# Sensor_Board.net
KiCad netlist of a schematic drawn in Altium Designer
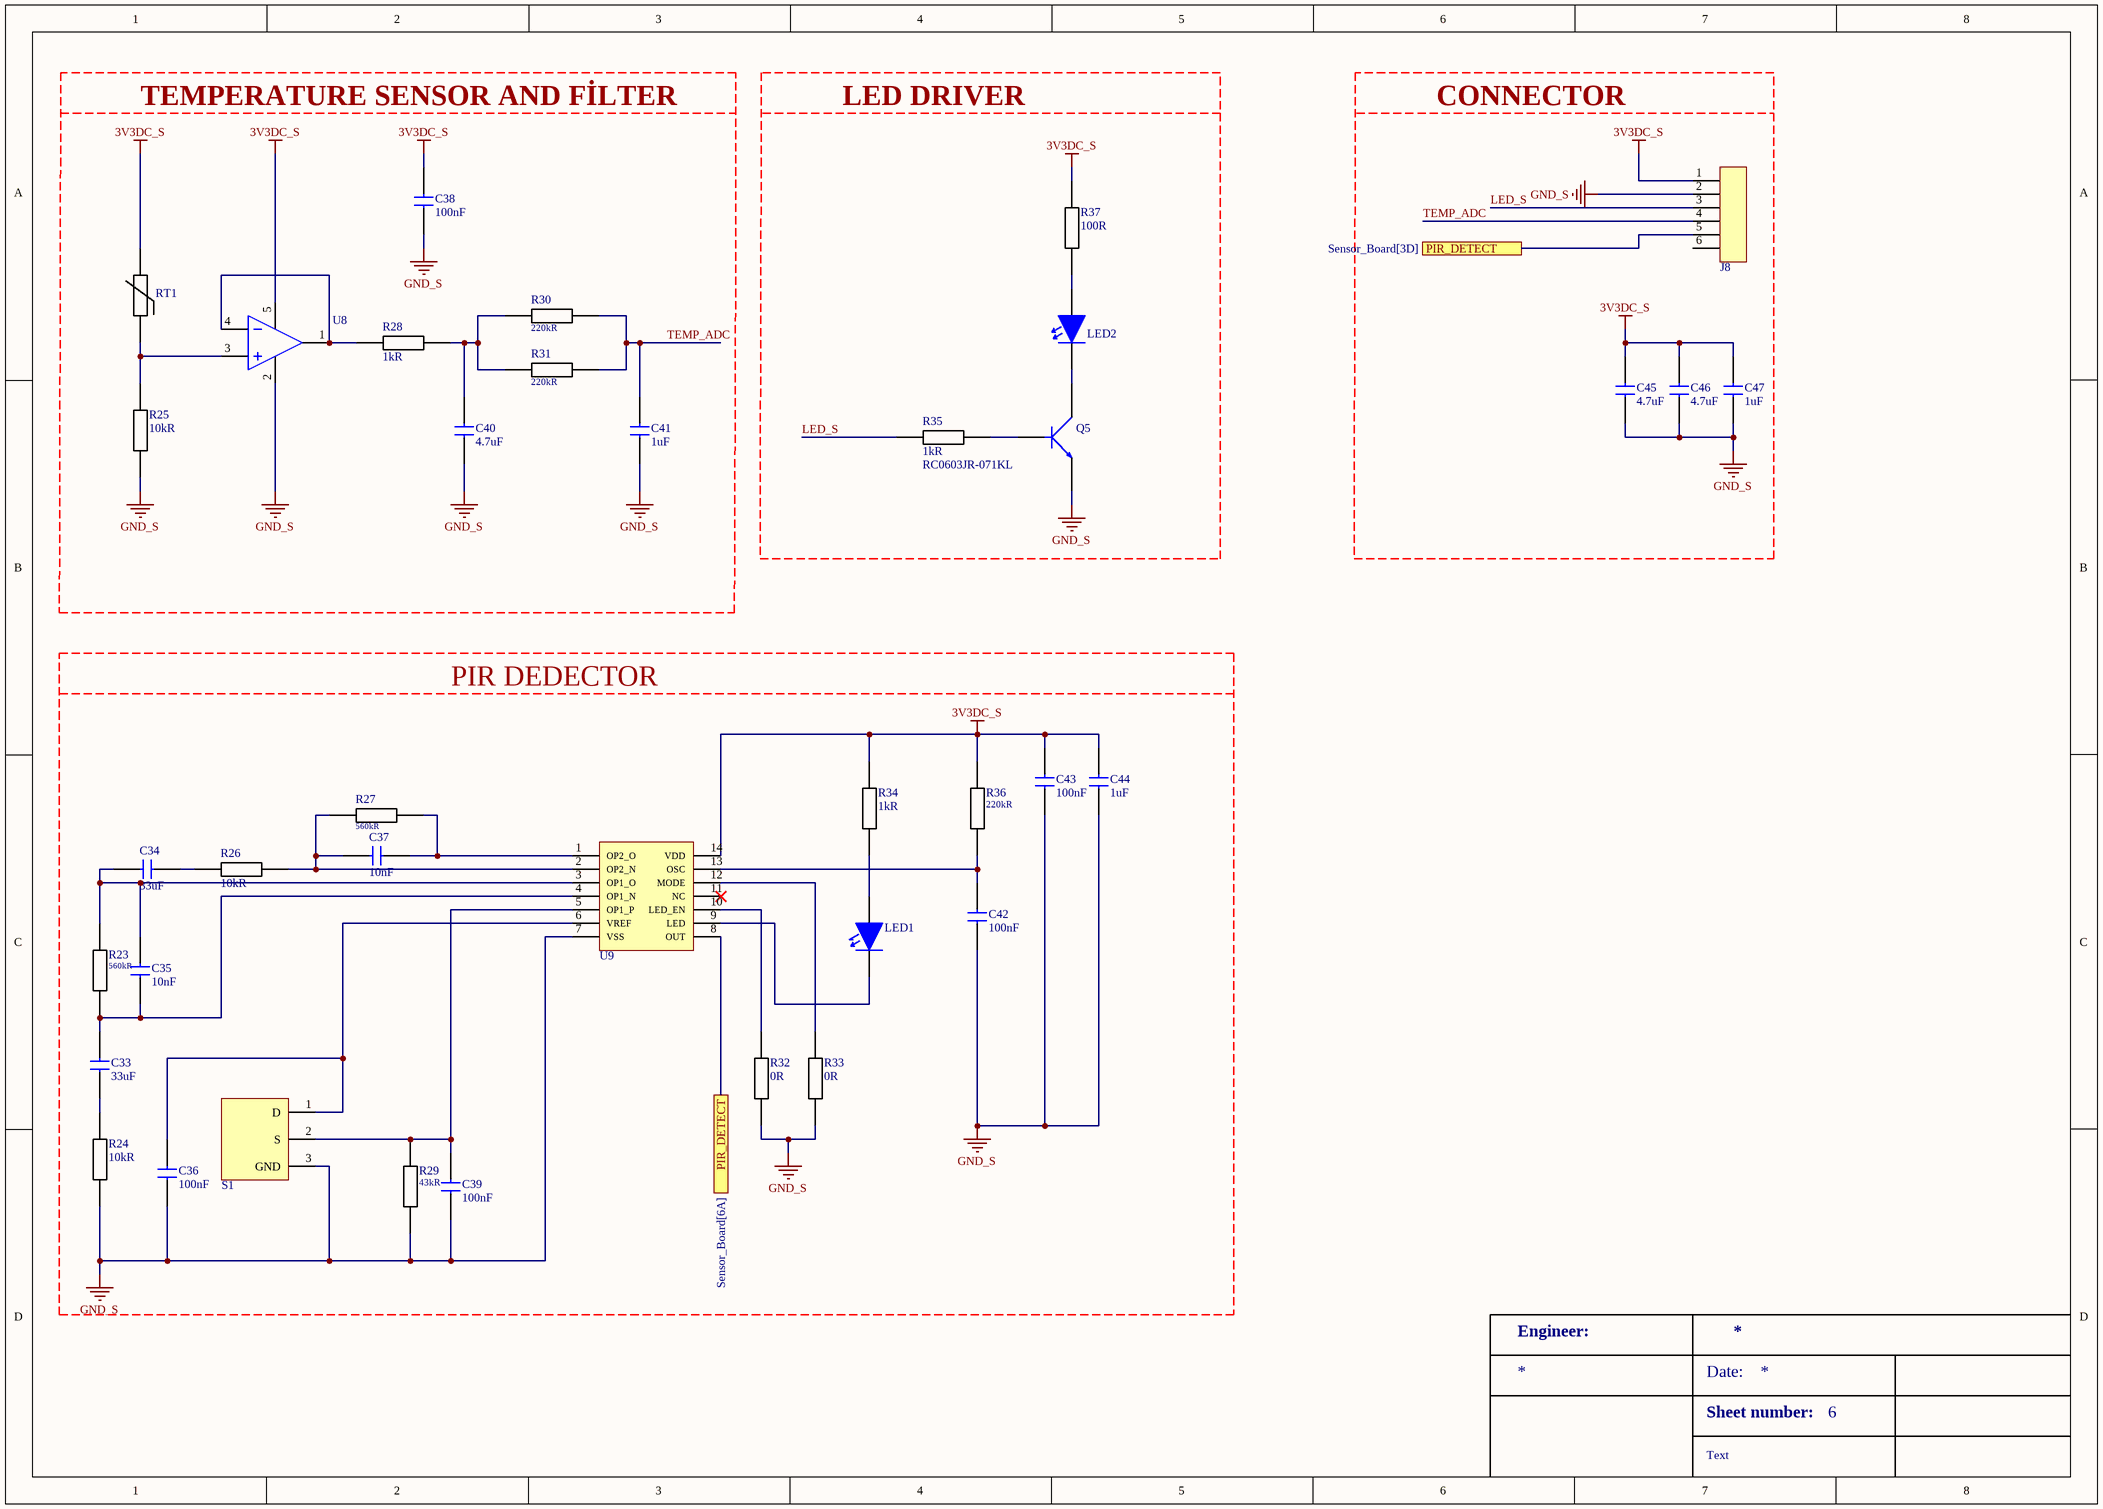
[diagram p0: Sensor_Board.SchDoc]

(export (version "E")
  (design (tool "Eeschema 10.0.6"))
  (components
    (comp (ref "C33")
      (value "33uF")
      (footprint "CAP_1206")
      (description "Ceramic Capacitor, 25V, 20% 33uF, Surface Mount, 1206")
      (fields
        (field (name "MANUFACTURER") "TDK")
        (field (name "MANUFACTURER PART NUMBER") "C3216X5R1E336M160AC")
        (field (name "DESIGNED BY") "Kerem")
      )
      (libsource (lib "library") (part "CAP_CER_33uF_1206"))
    )
    (comp (ref "C34")
      (value "33uF")
      (footprint "CAP_1206")
      (description "Ceramic Capacitor, 25V, 20% 33uF, Surface Mount, 1206")
      (fields
        (field (name "MANUFACTURER") "TDK")
        (field (name "MANUFACTURER PART NUMBER") "C3216X5R1E336M160AC")
        (field (name "DESIGNED BY") "Kerem")
      )
      (libsource (lib "library") (part "CAP_CER_33uF_1206"))
    )
    (comp (ref "C35")
      (value "10nF")
      (footprint "CAP_0603")
      (description "Ceramic Capacitor,16V, 10%, 0.01uF, Surface Mount, 0603")
      (fields
        (field (name "MANUFACTURER") "Walsin Technologies")
        (field (name "MANUFACTURER PART NUMBER") "0603B103K160CT")
        (field (name "DESIGNED BY") "Kerem")
      )
      (libsource (lib "library") (part "CAP_CER_10nF_0603"))
    )
    (comp (ref "C36")
      (value "100nF")
      (footprint "CAP_0805")
      (description "Ceramic Capacitor,50V, %10, 0.1uF, Surface Mount, 0805")
      (fields
        (field (name "MANUFACTURER") "Samsung")
        (field (name "MANUFACTURER PART NUMBER") "CL21B104KBCNNNC")
        (field (name "DESIGNED BY") "Kerem")
      )
      (libsource (lib "library") (part "CAP_CER_100nF_0805"))
    )
    (comp (ref "C37")
      (value "10nF")
      (footprint "CAP_0603")
      (description "Ceramic Capacitor,16V, 10%, 0.01uF, Surface Mount, 0603")
      (fields
        (field (name "MANUFACTURER") "Walsin Technologies")
        (field (name "MANUFACTURER PART NUMBER") "0603B103K160CT")
        (field (name "DESIGNED BY") "Kerem")
      )
      (libsource (lib "library") (part "CAP_CER_10nF_0603"))
    )
    (comp (ref "C38")
      (value "100nF")
      (footprint "CAP_0805")
      (description "Ceramic Capacitor,50V, %10, 0.1uF, Surface Mount, 0805")
      (fields
        (field (name "MANUFACTURER") "Samsung")
        (field (name "MANUFACTURER PART NUMBER") "CL21B104KBCNNNC")
        (field (name "DESIGNED BY") "Kerem")
      )
      (libsource (lib "library") (part "CAP_CER_100nF_0805"))
    )
    (comp (ref "C39")
      (value "100nF")
      (footprint "CAP_0805")
      (description "Ceramic Capacitor,50V, %10, 0.1uF, Surface Mount, 0805")
      (fields
        (field (name "MANUFACTURER") "Samsung")
        (field (name "MANUFACTURER PART NUMBER") "CL21B104KBCNNNC")
        (field (name "DESIGNED BY") "Kerem")
      )
      (libsource (lib "library") (part "CAP_CER_100nF_0805"))
    )
    (comp (ref "C40")
      (value "4.7uF")
      (footprint "CAP_0805")
      (description "CAP CER 4.7uF,%10, Surface Mount, 0805")
      (fields
        (field (name "MANUFACTURER") "Samsung")
        (field (name "MANUFACTURER PART NUMBER") "CL21A475KAQNNNE")
        (field (name "DESIGNED BY") "Kerem")
      )
      (libsource (lib "library") (part "CAP_CER_4.7uF_0805"))
    )
    (comp (ref "C41")
      (value "1uF")
      (footprint "CAP_0805")
      (description "Cap CER, 1uF, 16V, 0805;")
      (fields
        (field (name "MANUFACTURER") "KEMET")
        (field (name "MANUFACTURER PART NUMBER") "CHA08C105K4RXL7189")
        (field (name "DESIGNED BY") "Kerem")
      )
      (libsource (lib "library") (part "CAP_CER_1uF_0805"))
    )
    (comp (ref "C42")
      (value "100nF")
      (footprint "CAP_0805")
      (description "Ceramic Capacitor,50V, %10, 0.1uF, Surface Mount, 0805")
      (fields
        (field (name "MANUFACTURER") "Samsung")
        (field (name "MANUFACTURER PART NUMBER") "CL21B104KBCNNNC")
        (field (name "DESIGNED BY") "Kerem")
      )
      (libsource (lib "library") (part "CAP_CER_100nF_0805"))
    )
    (comp (ref "C43")
      (value "100nF")
      (footprint "CAP_0805")
      (description "Ceramic Capacitor,50V, %10, 0.1uF, Surface Mount, 0805")
      (fields
        (field (name "MANUFACTURER") "Samsung")
        (field (name "MANUFACTURER PART NUMBER") "CL21B104KBCNNNC")
        (field (name "DESIGNED BY") "Kerem")
      )
      (libsource (lib "library") (part "CAP_CER_100nF_0805"))
    )
    (comp (ref "C44")
      (value "1uF")
      (footprint "CAP_0805")
      (description "Cap CER, 1uF, 16V, 0805;")
      (fields
        (field (name "MANUFACTURER") "KEMET")
        (field (name "MANUFACTURER PART NUMBER") "CHA08C105K4RXL7189")
        (field (name "DESIGNED BY") "Kerem")
      )
      (libsource (lib "library") (part "CAP_CER_1uF_0805"))
    )
    (comp (ref "C45")
      (value "4.7uF")
      (footprint "CAP_0805")
      (description "CAP CER 4.7uF,%10, Surface Mount, 0805")
      (fields
        (field (name "MANUFACTURER") "Samsung")
        (field (name "MANUFACTURER PART NUMBER") "CL21A475KAQNNNE")
        (field (name "DESIGNED BY") "Kerem")
      )
      (libsource (lib "library") (part "CAP_CER_4.7uF_0805"))
    )
    (comp (ref "C46")
      (value "4.7uF")
      (footprint "CAP_0805")
      (description "CAP CER 4.7uF,%10, Surface Mount, 0805")
      (fields
        (field (name "MANUFACTURER") "Samsung")
        (field (name "MANUFACTURER PART NUMBER") "CL21A475KAQNNNE")
        (field (name "DESIGNED BY") "Kerem")
      )
      (libsource (lib "library") (part "CAP_CER_4.7uF_0805"))
    )
    (comp (ref "C47")
      (value "1uF")
      (footprint "CAP_0805")
      (description "Cap CER, 1uF, 16V, 0805;")
      (fields
        (field (name "MANUFACTURER") "KEMET")
        (field (name "MANUFACTURER PART NUMBER") "CHA08C105K4RXL7189")
        (field (name "DESIGNED BY") "Kerem")
      )
      (libsource (lib "library") (part "CAP_CER_1uF_0805"))
    )
    (comp (ref "J8")
      (value "64800611622")
      (footprint "64800611622")
      (description "WR-WTB Wire-to-Board Connectors 1.50 mm")
      (fields (field (name "MANUFACTURER") "Wurth Electronics") (field (name "DESIGNED BY") "Kerem"))
      (libsource (lib "library") (part "64800611622_CONN_6PINS"))
    )
    (comp (ref "LED1")
      (value "LTST-C171GKT")
      (footprint "LED_GREEN 0805")
      (description "Single Color LED, Green, Water Clear, 1.4mm")
      (fields (field (name "MANUFACTURER") "Vishay Lite-On") (field (name "DESIGNED BY") "Kerem"))
      (libsource (lib "library") (part "LED_GREEN_0805"))
    )
    (comp (ref "LED2")
      (value "LH R974-LP-1")
      (footprint "LED_RED 0805")
      (fields (field (name "DESIGNED BY") "Kerem"))
      (libsource (lib "library") (part "LED_RED_0805"))
    )
    (comp (ref "Q5")
      (value "MMBT3904-7-F")
      (footprint "SOT-23F")
      (description "Small Signal Bipolar Transistor, 0.2A I(C), 40V V(BR)CEO, 1-Element, NPN, Silicon")
      (fields (field (name "MANUFACTURER") "Diodes Zetex") (field (name "DESIGNED BY") "Kerem"))
      (libsource (lib "library") (part "MMBT3904-7-F"))
    )
    (comp (ref "R23")
      (value "560kR")
      (footprint "RES_0603")
      (description "0.1W, 560000ohm, 75V, 5%, Surface Mount, 0603")
      (fields
        (field (name "MANUFACTURER") "Yageo")
        (field (name "MANUFACTURER PART NUMBER") "RC0603JR-07560KL")
        (field (name "DESIGNED BY") "Kerem")
      )
      (libsource (lib "library") (part "RES_560K OHM_0603"))
    )
    (comp (ref "R24")
      (value "10kR")
      (footprint "RES_0603")
      (fields
        (field (name "MANUFACTURER") "Yageo")
        (field (name "MANUFACTURER PART NUMBER") "RC0603FR-0710KL")
        (field (name "TOLERANCE") "1%")
        (field (name "DESIGNED BY") "Kerem")
      )
      (libsource (lib "library") (part "RES 10K OHM 0603"))
    )
    (comp (ref "R25")
      (value "10kR")
      (footprint "RES_0603")
      (fields
        (field (name "MANUFACTURER") "Yageo")
        (field (name "MANUFACTURER PART NUMBER") "RC0603FR-0710KL")
        (field (name "TOLERANCE") "1%")
        (field (name "DESIGNED BY") "Kerem")
      )
      (libsource (lib "library") (part "RES 10K OHM 0603"))
    )
    (comp (ref "R26")
      (value "10kR")
      (footprint "RES_0603")
      (fields
        (field (name "MANUFACTURER") "Yageo")
        (field (name "MANUFACTURER PART NUMBER") "RC0603FR-0710KL")
        (field (name "TOLERANCE") "1%")
        (field (name "DESIGNED BY") "Kerem")
      )
      (libsource (lib "library") (part "RES 10K OHM 0603"))
    )
    (comp (ref "R27")
      (value "560kR")
      (footprint "RES_0603")
      (description "0.1W, 560000ohm, 75V, 5%, Surface Mount, 0603")
      (fields
        (field (name "MANUFACTURER") "Yageo")
        (field (name "MANUFACTURER PART NUMBER") "RC0603JR-07560KL")
        (field (name "DESIGNED BY") "Kerem")
      )
      (libsource (lib "library") (part "RES_560K OHM_0603"))
    )
    (comp (ref "R28")
      (value "1kR")
      (footprint "RES_0603")
      (description "0.1W, 1000ohm, 75V, 5%, Surface Mount, 0603")
      (fields
        (field (name "MANUFACTURER") "Yageo")
        (field (name "MANUFACTURER PART NUMBER") "RC0603JR-071KL")
        (field (name "DESIGNED BY") "Kerem")
      )
      (libsource (lib "library") (part "RES_1K OHM_0603"))
    )
    (comp (ref "R29")
      (value "43kR")
      (footprint "RES_0603")
      (description "0.1W, 43000ohm, 75V, 5%, Surface Mount, 0603")
      (fields
        (field (name "MANUFACTURER") "Yageo")
        (field (name "MANUFACTURER PART NUMBER") "RC0603JR-0743KL")
        (field (name "DESIGNED BY") "Kerem")
      )
      (libsource (lib "library") (part "RES_43K OHM_0603"))
    )
    (comp (ref "R30")
      (value "220kR")
      (footprint "RES_0603")
      (description "0.1W, 220000ohm, 75V, 5%, Surface Mount, 0603")
      (fields
        (field (name "MANUFACTURER") "Yageo")
        (field (name "MANUFACTURER PART NUMBER") "RC0603JR-07220KL")
        (field (name "DESIGNED BY") "Kerem")
      )
      (libsource (lib "library") (part "RES_220K OHM_0603"))
    )
    (comp (ref "R31")
      (value "220kR")
      (footprint "RES_0603")
      (description "0.1W, 220000ohm, 75V, 5%, Surface Mount, 0603")
      (fields
        (field (name "MANUFACTURER") "Yageo")
        (field (name "MANUFACTURER PART NUMBER") "RC0603JR-07220KL")
        (field (name "DESIGNED BY") "Kerem")
      )
      (libsource (lib "library") (part "RES_220K OHM_0603"))
    )
    (comp (ref "R32")
      (value "0R")
      (footprint "RES_0603")
      (description "Metal Glaze/thick Film, 0.1W, 0ohm, Surface Mount, 0603")
      (fields
        (field (name "MANUFACTURER") "Yageo")
        (field (name "MANUFACTURER PART NUMBER") "RC0603JR-070RL")
        (field (name "DESIGNED BY") "Kerem")
      )
      (libsource (lib "library") (part "RES_0 OHM_0603"))
    )
    (comp (ref "R33")
      (value "0R")
      (footprint "RES_0603")
      (description "Metal Glaze/thick Film, 0.1W, 0ohm, Surface Mount, 0603")
      (fields
        (field (name "MANUFACTURER") "Yageo")
        (field (name "MANUFACTURER PART NUMBER") "RC0603JR-070RL")
        (field (name "DESIGNED BY") "Kerem")
      )
      (libsource (lib "library") (part "RES_0 OHM_0603"))
    )
    (comp (ref "R34")
      (value "1kR")
      (footprint "RES_0603")
      (description "0.1W, 1000ohm, 75V, 5%, Surface Mount, 0603")
      (fields
        (field (name "MANUFACTURER") "Yageo")
        (field (name "MANUFACTURER PART NUMBER") "RC0603JR-071KL")
        (field (name "DESIGNED BY") "Kerem")
      )
      (libsource (lib "library") (part "RES_1K OHM_0603"))
    )
    (comp (ref "R35")
      (value "RC0603JR-071KL")
      (footprint "RES_0603")
      (description "0.1W, 1000ohm, 75V, 5%, Surface Mount, 0603")
      (fields
        (field (name "MANUFACTURER") "Yageo")
        (field (name "TOLERANCE") "5%")
        (field (name "ALTIUM_VALUE") "1kR")
        (field (name "DESIGNED BY") "Kerem")
      )
      (libsource (lib "library") (part "RES_1K OHM_0603"))
    )
    (comp (ref "R36")
      (value "220kR")
      (footprint "RES_0603")
      (description "0.1W, 220000ohm, 75V, 5%, Surface Mount, 0603")
      (fields
        (field (name "MANUFACTURER") "Yageo")
        (field (name "MANUFACTURER PART NUMBER") "RC0603JR-07220KL")
        (field (name "DESIGNED BY") "Kerem")
      )
      (libsource (lib "library") (part "RES_220K OHM_0603"))
    )
    (comp (ref "R37")
      (value "100R")
      (footprint "RES_0603")
      (description "0.1W, 100ohm, 75V, 1% Surface Mount, 0603")
      (fields
        (field (name "MANUFACTURER") "Yageo")
        (field (name "MANUFACTURER PART NUMBER") "RC0603FR-07100RL")
        (field (name "DESIGNED BY") "Kerem")
      )
      (libsource (lib "library") (part "RES_100 OHM_0603"))
    )
    (comp (ref "RT1")
      (value "TFPT 1206L1002FM")
      (footprint "RES-1206")
      (description "PTC Thermistor, 10000ohm, Surface Mount 1206")
      (fields
        (field (name "MANUFACTURER") "Vishay Dale")
        (field (name "MANUFACTURER PART NUMBER") "TFPT1206L1002FM")
        (field (name "DESIGNED BY") "Kerem")
      )
      (libsource (lib "library") (part "TFPT 1206L1002FM"))
    )
    (comp (ref "S1")
      (value "LHI 878/3902")
      (footprint "LHI 878/3902")
      (description "Sensor Pyro Detector Dual Motion")
      (fields
        (field (name "MANUFACTURER") "Excelitas Technology")
        (field (name "DESIGNED BY") "Kerem")
        (field (name "COMPONENTLINK1URL") "file:///C:/Users/KEREM/Downloads/PYD_1388___7083_Dual_Element_Pyrodetector_Datasheet.pdf")
      )
      (libsource (lib "library") (part "LHI 878/3902"))
    )
    (comp (ref "U8")
      (value "OPA314AIDBVR")
      (footprint "SOT23-5")
      (description "Operational Amplifier, 1 Func, 2500uV Offset-Max, CMOS, PDSO5")
      (fields
        (field (name "MANUFACTURER") "Texas Instruments")
        (field (name "POWER") "No")
        (field (name "DESIGNED BY") "Kerem")
      )
      (libsource (lib "library") (part "OPA314"))
    )
    (comp (ref "U9")
      (value "NCS36000DRG")
      (footprint "SOIC14")
      (description "PIR Controller Analog Circuit, 1 Func, CMOS, PDSO14")
      (fields (field (name "MANUFACTURER") "ON Semiconductor") (field (name "DESIGNED BY") "Kerem"))
      (libsource (lib "library") (part "NCS36000"))
    )
  )
  (nets
    (net (code "1") (name "/LED_S") (class "Default")
      (node (ref "J8") (pin "3") (pinfunction "3_3") (pintype "passive"))
      (node (ref "R35") (pin "1") (pinfunction "1_1") (pintype "passive"))
    )
    (net (code "2") (name "/PIR_DETECT") (class "Default")
      (node (ref "J8") (pin "5") (pinfunction "5_5") (pintype "passive"))
      (node (ref "U9") (pin "8") (pinfunction "OUT_8") (pintype "passive"))
    )
    (net (code "3") (name "/TEMP_ADC") (class "Default")
      (node (ref "C41") (pin "2") (pinfunction "2_2") (pintype "passive"))
      (node (ref "J8") (pin "4") (pinfunction "4_4") (pintype "passive"))
      (node (ref "R30") (pin "2") (pinfunction "2_2") (pintype "passive"))
      (node (ref "R31") (pin "2") (pinfunction "2_2") (pintype "passive"))
    )
    (net (code "4") (name "3V3DC_S") (class "Default")
      (node (ref "C38") (pin "2") (pinfunction "2_2") (pintype "passive"))
      (node (ref "C43") (pin "2") (pinfunction "2_2") (pintype "passive"))
      (node (ref "C44") (pin "2") (pinfunction "2_2") (pintype "passive"))
      (node (ref "C45") (pin "2") (pinfunction "2_2") (pintype "passive"))
      (node (ref "C46") (pin "2") (pinfunction "2_2") (pintype "passive"))
      (node (ref "C47") (pin "2") (pinfunction "2_2") (pintype "passive"))
      (node (ref "J8") (pin "1") (pinfunction "1_1") (pintype "passive"))
      (node (ref "R34") (pin "2") (pinfunction "2_2") (pintype "passive"))
      (node (ref "R36") (pin "1") (pinfunction "1_1") (pintype "passive"))
      (node (ref "R37") (pin "2") (pinfunction "2_2") (pintype "passive"))
      (node (ref "RT1") (pin "2") (pinfunction "2_2") (pintype "passive"))
      (node (ref "U8") (pin "5") (pinfunction "5_5") (pintype "passive"))
      (node (ref "U9") (pin "14") (pinfunction "VDD_14") (pintype "passive"))
    )
    (net (code "5") (name "GND_S") (class "Default")
      (node (ref "C36") (pin "1") (pinfunction "1_1") (pintype "passive"))
      (node (ref "C38") (pin "1") (pinfunction "1_1") (pintype "passive"))
      (node (ref "C39") (pin "1") (pinfunction "1_1") (pintype "passive"))
      (node (ref "C40") (pin "1") (pinfunction "1_1") (pintype "passive"))
      (node (ref "C41") (pin "1") (pinfunction "1_1") (pintype "passive"))
      (node (ref "C42") (pin "1") (pinfunction "1_1") (pintype "passive"))
      (node (ref "C43") (pin "1") (pinfunction "1_1") (pintype "passive"))
      (node (ref "C44") (pin "1") (pinfunction "1_1") (pintype "passive"))
      (node (ref "C45") (pin "1") (pinfunction "1_1") (pintype "passive"))
      (node (ref "C46") (pin "1") (pinfunction "1_1") (pintype "passive"))
      (node (ref "C47") (pin "1") (pinfunction "1_1") (pintype "passive"))
      (node (ref "J8") (pin "2") (pinfunction "2_2") (pintype "passive"))
      (node (ref "Q5") (pin "2") (pinfunction "E_2") (pintype "passive"))
      (node (ref "R24") (pin "1") (pinfunction "1_1") (pintype "passive"))
      (node (ref "R25") (pin "1") (pinfunction "1_1") (pintype "passive"))
      (node (ref "R29") (pin "1") (pinfunction "1_1") (pintype "passive"))
      (node (ref "R32") (pin "1") (pinfunction "1_1") (pintype "passive"))
      (node (ref "R33") (pin "1") (pinfunction "1_1") (pintype "passive"))
      (node (ref "S1") (pin "3") (pinfunction "GND_3") (pintype "passive"))
      (node (ref "U8") (pin "2") (pinfunction "2_2") (pintype "passive"))
      (node (ref "U9") (pin "7") (pinfunction "VSS_7") (pintype "passive"))
    )
    (net (code "6") (name "Net-(C33-Pad1)") (class "Default")
      (node (ref "C33") (pin "1") (pinfunction "1_1") (pintype "passive"))
      (node (ref "R24") (pin "2") (pinfunction "2_2") (pintype "passive"))
    )
    (net (code "7") (name "Net-(C34-Pad2)") (class "Default")
      (node (ref "C34") (pin "2") (pinfunction "2_2") (pintype "passive"))
      (node (ref "R26") (pin "1") (pinfunction "1_1") (pintype "passive"))
    )
    (net (code "8") (name "Net-(C40-Pad2)") (class "Default")
      (node (ref "C40") (pin "2") (pinfunction "2_2") (pintype "passive"))
      (node (ref "R28") (pin "2") (pinfunction "2_2") (pintype "passive"))
      (node (ref "R30") (pin "1") (pinfunction "1_1") (pintype "passive"))
      (node (ref "R31") (pin "1") (pinfunction "1_1") (pintype "passive"))
    )
    (net (code "9") (name "Net-(LED1-Pad2)") (class "Default")
      (node (ref "LED1") (pin "2") (pinfunction "2_2") (pintype "passive"))
      (node (ref "R34") (pin "1") (pinfunction "1_1") (pintype "passive"))
    )
    (net (code "10") (name "Net-(LED2-Pad2)") (class "Default")
      (node (ref "LED2") (pin "2") (pinfunction "2_2") (pintype "passive"))
      (node (ref "R37") (pin "1") (pinfunction "1_1") (pintype "passive"))
    )
    (net (code "11") (name "Net-(Q5-B)") (class "Default")
      (node (ref "Q5") (pin "1") (pinfunction "B_1") (pintype "passive"))
      (node (ref "R35") (pin "2") (pinfunction "2_2") (pintype "passive"))
    )
    (net (code "12") (name "Net-(Q5-C)") (class "Default")
      (node (ref "LED2") (pin "1") (pinfunction "1_1") (pintype "passive"))
      (node (ref "Q5") (pin "3") (pinfunction "C_3") (pintype "passive"))
    )
    (net (code "13") (name "Net-(R25-Pad2)") (class "Default")
      (node (ref "R25") (pin "2") (pinfunction "2_2") (pintype "passive"))
      (node (ref "RT1") (pin "1") (pinfunction "1_1") (pintype "passive"))
      (node (ref "U8") (pin "3") (pinfunction "3_3") (pintype "passive"))
    )
    (net (code "14") (name "Net-(R28-Pad1)") (class "Default")
      (node (ref "R28") (pin "1") (pinfunction "1_1") (pintype "passive"))
      (node (ref "U8") (pin "1") (pinfunction "1_1") (pintype "passive"))
      (node (ref "U8") (pin "4") (pinfunction "4_4") (pintype "passive"))
    )
    (net (code "15") (name "Net-(S1-D)") (class "Default")
      (node (ref "C36") (pin "2") (pinfunction "2_2") (pintype "passive"))
      (node (ref "S1") (pin "1") (pinfunction "D_1") (pintype "passive"))
      (node (ref "U9") (pin "6") (pinfunction "VREF_6") (pintype "passive"))
    )
    (net (code "16") (name "Net-(S1-S)") (class "Default")
      (node (ref "C39") (pin "2") (pinfunction "2_2") (pintype "passive"))
      (node (ref "R29") (pin "2") (pinfunction "2_2") (pintype "passive"))
      (node (ref "S1") (pin "2") (pinfunction "S_2") (pintype "passive"))
      (node (ref "U9") (pin "5") (pinfunction "OP1_P_5") (pintype "passive"))
    )
    (net (code "17") (name "Net-(U9-LED)") (class "Default")
      (node (ref "LED1") (pin "1") (pinfunction "1_1") (pintype "passive"))
      (node (ref "U9") (pin "9") (pinfunction "LED_9") (pintype "passive"))
    )
    (net (code "18") (name "Net-(U9-LED_EN)") (class "Default")
      (node (ref "R32") (pin "2") (pinfunction "2_2") (pintype "passive"))
      (node (ref "U9") (pin "10") (pinfunction "LED_EN_10") (pintype "passive"))
    )
    (net (code "19") (name "Net-(U9-MODE)") (class "Default")
      (node (ref "R33") (pin "2") (pinfunction "2_2") (pintype "passive"))
      (node (ref "U9") (pin "12") (pinfunction "MODE_12") (pintype "passive"))
    )
    (net (code "20") (name "Net-(U9-OP1_N)") (class "Default")
      (node (ref "C33") (pin "2") (pinfunction "2_2") (pintype "passive"))
      (node (ref "C35") (pin "1") (pinfunction "1_1") (pintype "passive"))
      (node (ref "R23") (pin "1") (pinfunction "1_1") (pintype "passive"))
      (node (ref "U9") (pin "4") (pinfunction "OP1_N_4") (pintype "passive"))
    )
    (net (code "21") (name "Net-(U9-OP1_O)") (class "Default")
      (node (ref "C34") (pin "1") (pinfunction "1_1") (pintype "passive"))
      (node (ref "C35") (pin "2") (pinfunction "2_2") (pintype "passive"))
      (node (ref "R23") (pin "2") (pinfunction "2_2") (pintype "passive"))
      (node (ref "U9") (pin "3") (pinfunction "OP1_O_3") (pintype "passive"))
    )
    (net (code "22") (name "Net-(U9-OP2_N)") (class "Default")
      (node (ref "C37") (pin "1") (pinfunction "1_1") (pintype "passive"))
      (node (ref "R26") (pin "2") (pinfunction "2_2") (pintype "passive"))
      (node (ref "R27") (pin "1") (pinfunction "1_1") (pintype "passive"))
      (node (ref "U9") (pin "2") (pinfunction "OP2_N_2") (pintype "passive"))
    )
    (net (code "23") (name "Net-(U9-OP2_O)") (class "Default")
      (node (ref "C37") (pin "2") (pinfunction "2_2") (pintype "passive"))
      (node (ref "R27") (pin "2") (pinfunction "2_2") (pintype "passive"))
      (node (ref "U9") (pin "1") (pinfunction "OP2_O_1") (pintype "passive"))
    )
    (net (code "24") (name "Net-(U9-OSC)") (class "Default")
      (node (ref "C42") (pin "2") (pinfunction "2_2") (pintype "passive"))
      (node (ref "R36") (pin "2") (pinfunction "2_2") (pintype "passive"))
      (node (ref "U9") (pin "13") (pinfunction "OSC_13") (pintype "passive"))
    )
    (net (code "25") (name "unconnected-(J8-Pad6)") (class "Default")
      (node (ref "J8") (pin "6") (pinfunction "6_6") (pintype "passive"))
    )
    (net (code "26") (name "unconnected-(U9-NC-Pad11)") (class "Default")
      (node (ref "U9") (pin "11") (pinfunction "NC_11") (pintype "passive+no_connect"))
    )
  )
)
